# Base_Board_RevD.net
KiCad netlist of a schematic drawn in EAGLE
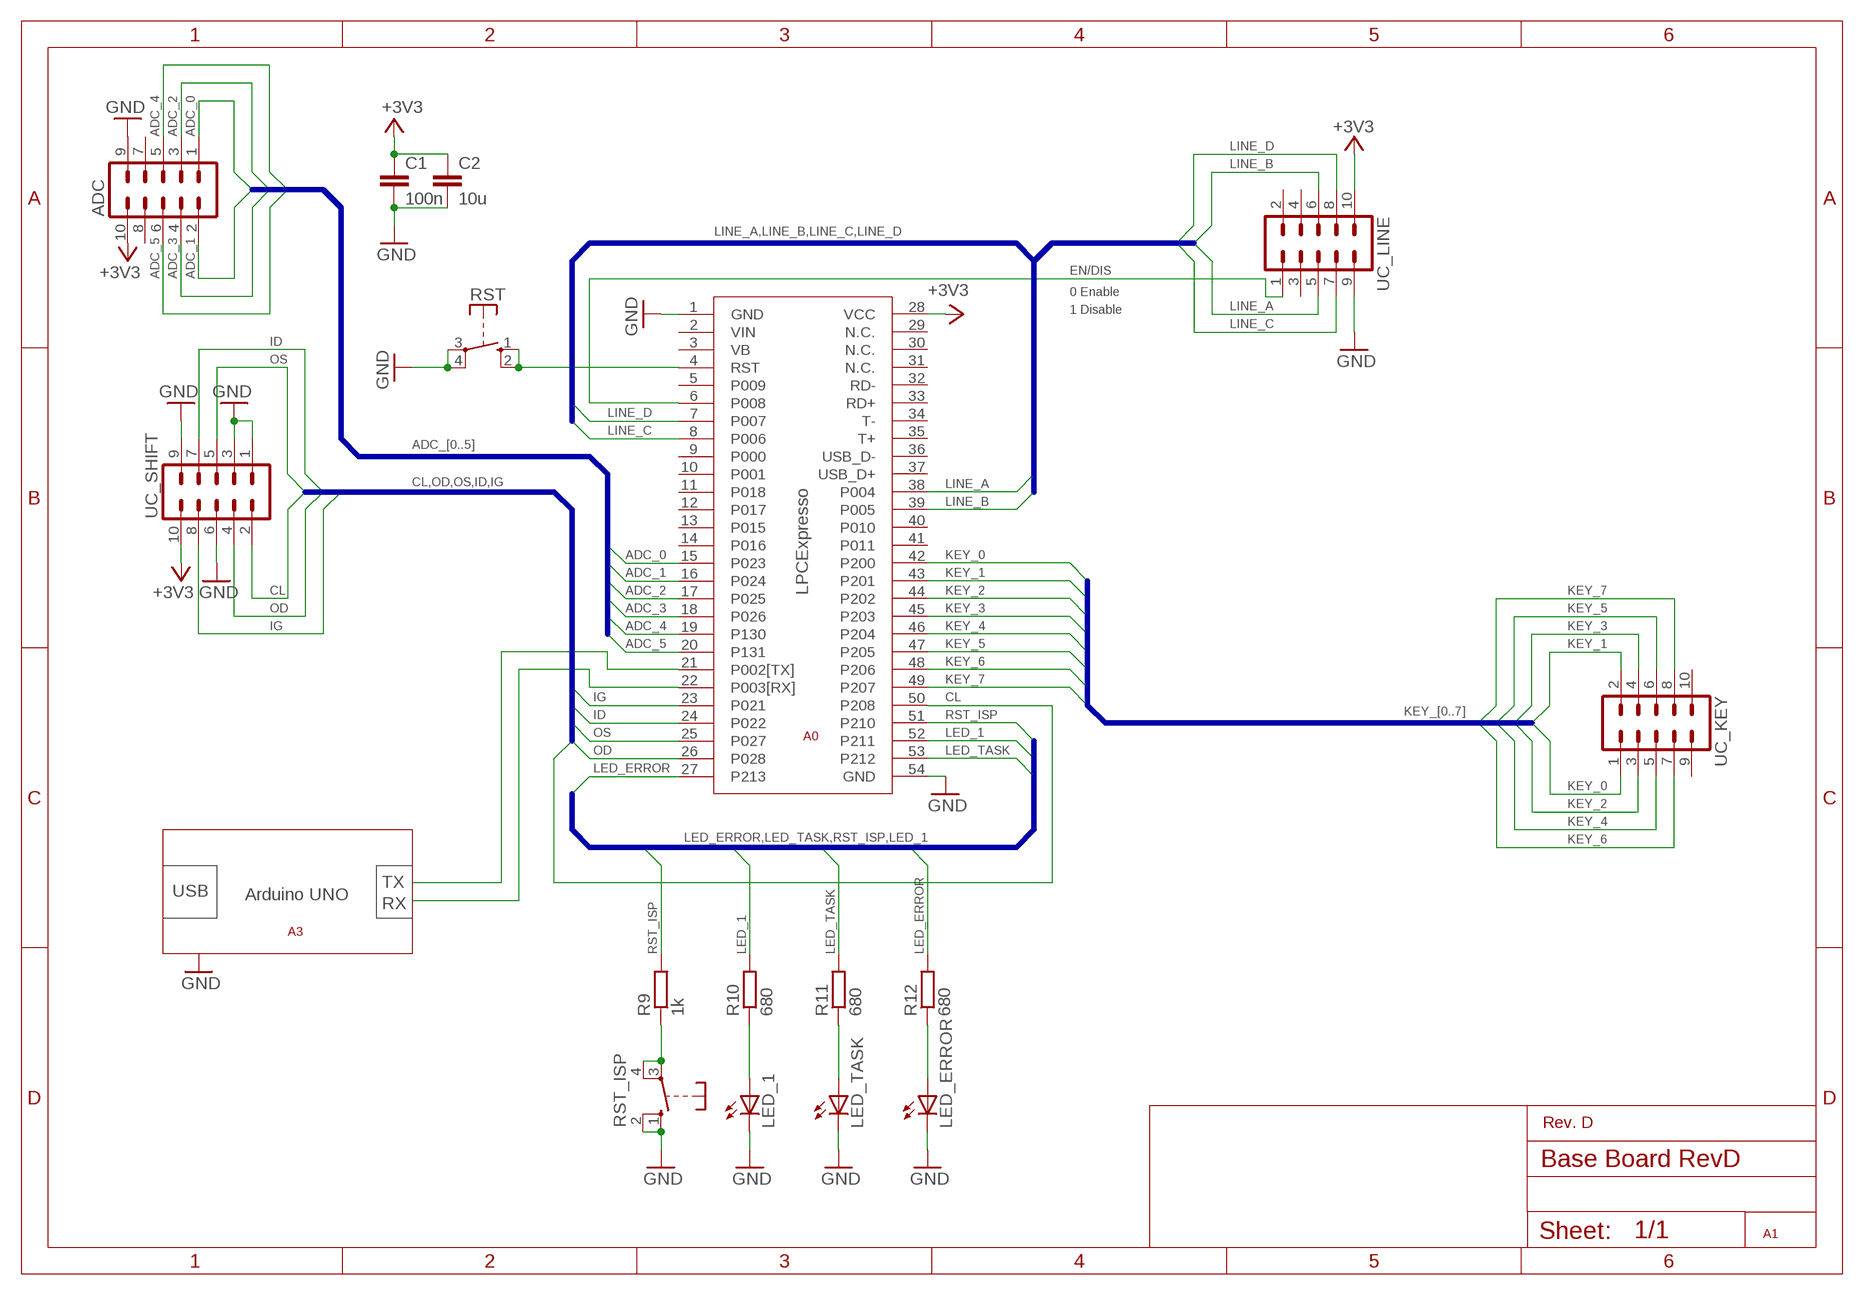
[diagram p0: schematic, sheet 1]

(export (version "E")
  (design (tool "Eeschema 10.0.6"))
  (components
    (comp (ref "ADC")
      (value "ML10")
      (footprint "eagle-import:ML10")
      (libsource (lib "eagle-import") (part "ML10"))
    )
    (comp (ref "C1")
      (value "100n")
      (footprint "eagle-import:C025-024X044")
      (libsource (lib "eagle-import") (part "C-EU025-024X044"))
    )
    (comp (ref "C2")
      (value "10u")
      (footprint "eagle-import:C025-024X044")
      (libsource (lib "eagle-import") (part "C-EU025-024X044"))
    )
    (comp (ref "LED_1")
      (value "LED5MM")
      (footprint "eagle-import:LED5MM")
      (libsource (lib "eagle-import") (part "LED5MM"))
    )
    (comp (ref "LED_ERROR")
      (value "LED5MM")
      (footprint "eagle-import:LED5MM")
      (libsource (lib "eagle-import") (part "LED5MM"))
    )
    (comp (ref "LED_TASK")
      (value "LED5MM")
      (footprint "eagle-import:LED5MM")
      (libsource (lib "eagle-import") (part "LED5MM"))
    )
    (comp (ref "R9")
      (value "1k")
      (footprint "eagle-import:0204_5")
      (libsource (lib "eagle-import") (part "R-EU_0204/5"))
    )
    (comp (ref "R10")
      (value "680")
      (footprint "eagle-import:0204_5")
      (libsource (lib "eagle-import") (part "R-EU_0204/5"))
    )
    (comp (ref "R11")
      (value "680")
      (footprint "eagle-import:0204_5")
      (libsource (lib "eagle-import") (part "R-EU_0204/5"))
    )
    (comp (ref "R12")
      (value "680")
      (footprint "eagle-import:0204_5")
      (libsource (lib "eagle-import") (part "R-EU_0204/5"))
    )
    (comp (ref "RST")
      (value "DT6")
      (footprint "eagle-import:DT6")
      (libsource (lib "eagle-import") (part "DT6"))
    )
    (comp (ref "RST_ISP")
      (value "DT6")
      (footprint "eagle-import:DT6")
      (libsource (lib "eagle-import") (part "DT6"))
    )
    (comp (ref "U$1")
      (value "LPCEXPRESSO")
      (footprint "eagle-import:LPCEXPRESSO")
      (libsource (lib "eagle-import") (part "LPCEXPRESSO"))
    )
    (comp (ref "UC_KEY")
      (value "ML10")
      (footprint "eagle-import:ML10")
      (libsource (lib "eagle-import") (part "ML10"))
    )
    (comp (ref "UC_LINE")
      (value "ML10")
      (footprint "eagle-import:ML10")
      (libsource (lib "eagle-import") (part "ML10"))
    )
    (comp (ref "UC_SHIFT")
      (value "ML10")
      (footprint "eagle-import:ML10")
      (libsource (lib "eagle-import") (part "ML10"))
    )
  )
  (nets
    (net (code "1") (name "+3V3") (class "Default")
      (node (ref "ADC") (pin "10") (pinfunction "10_10") (pintype "passive"))
      (node (ref "C1") (pin "1") (pinfunction "1_1") (pintype "passive"))
      (node (ref "C2") (pin "1") (pinfunction "1_1") (pintype "passive"))
      (node (ref "U$1") (pin "28") (pinfunction "VCC_28") (pintype "power_in"))
      (node (ref "UC_LINE") (pin "10") (pinfunction "10_10") (pintype "passive"))
      (node (ref "UC_SHIFT") (pin "10") (pinfunction "10_10") (pintype "passive"))
    )
    (net (code "2") (name "/ADC_0") (class "Default")
      (node (ref "ADC") (pin "1") (pinfunction "1_1") (pintype "passive"))
      (node (ref "U$1") (pin "15") (pinfunction "P023_15") (pintype "bidirectional"))
    )
    (net (code "3") (name "/ADC_1") (class "Default")
      (node (ref "ADC") (pin "2") (pinfunction "2_2") (pintype "passive"))
      (node (ref "U$1") (pin "16") (pinfunction "P024_16") (pintype "bidirectional"))
    )
    (net (code "4") (name "/ADC_2") (class "Default")
      (node (ref "ADC") (pin "3") (pinfunction "3_3") (pintype "passive"))
      (node (ref "U$1") (pin "17") (pinfunction "P025_17") (pintype "bidirectional"))
    )
    (net (code "5") (name "/ADC_3") (class "Default")
      (node (ref "ADC") (pin "4") (pinfunction "4_4") (pintype "passive"))
      (node (ref "U$1") (pin "18") (pinfunction "P026_18") (pintype "bidirectional"))
    )
    (net (code "6") (name "/ADC_4") (class "Default")
      (node (ref "ADC") (pin "5") (pinfunction "5_5") (pintype "passive"))
      (node (ref "U$1") (pin "19") (pinfunction "P130_19") (pintype "bidirectional"))
    )
    (net (code "7") (name "/ADC_5") (class "Default")
      (node (ref "ADC") (pin "6") (pinfunction "6_6") (pintype "passive"))
      (node (ref "U$1") (pin "20") (pinfunction "P131_20") (pintype "bidirectional"))
    )
    (net (code "9") (name "/CL") (class "Default")
      (node (ref "U$1") (pin "50") (pinfunction "P208_50") (pintype "bidirectional"))
      (node (ref "UC_SHIFT") (pin "2") (pinfunction "2_2") (pintype "passive"))
    )
    (net (code "10") (name "/EN{slash}DIS") (class "Default")
      (node (ref "U$1") (pin "6") (pinfunction "P008_6") (pintype "bidirectional"))
      (node (ref "UC_LINE") (pin "1") (pinfunction "1_1") (pintype "passive"))
    )
    (net (code "11") (name "/ID") (class "Default")
      (node (ref "U$1") (pin "24") (pinfunction "P022_24") (pintype "bidirectional"))
      (node (ref "UC_SHIFT") (pin "7") (pinfunction "7_7") (pintype "passive"))
    )
    (net (code "12") (name "/IG") (class "Default")
      (node (ref "U$1") (pin "23") (pinfunction "P021_23") (pintype "bidirectional"))
      (node (ref "UC_SHIFT") (pin "8") (pinfunction "8_8") (pintype "passive"))
    )
    (net (code "13") (name "/KEY_0") (class "Default")
      (node (ref "U$1") (pin "42") (pinfunction "P200_42") (pintype "bidirectional"))
      (node (ref "UC_KEY") (pin "1") (pinfunction "1_1") (pintype "passive"))
    )
    (net (code "14") (name "/KEY_1") (class "Default")
      (node (ref "U$1") (pin "43") (pinfunction "P201_43") (pintype "bidirectional"))
      (node (ref "UC_KEY") (pin "2") (pinfunction "2_2") (pintype "passive"))
    )
    (net (code "15") (name "/KEY_2") (class "Default")
      (node (ref "U$1") (pin "44") (pinfunction "P202_44") (pintype "bidirectional"))
      (node (ref "UC_KEY") (pin "3") (pinfunction "3_3") (pintype "passive"))
    )
    (net (code "16") (name "/KEY_3") (class "Default")
      (node (ref "U$1") (pin "45") (pinfunction "P203_45") (pintype "bidirectional"))
      (node (ref "UC_KEY") (pin "4") (pinfunction "4_4") (pintype "passive"))
    )
    (net (code "17") (name "/KEY_4") (class "Default")
      (node (ref "U$1") (pin "46") (pinfunction "P204_46") (pintype "bidirectional"))
      (node (ref "UC_KEY") (pin "5") (pinfunction "5_5") (pintype "passive"))
    )
    (net (code "18") (name "/KEY_5") (class "Default")
      (node (ref "U$1") (pin "47") (pinfunction "P205_47") (pintype "bidirectional"))
      (node (ref "UC_KEY") (pin "6") (pinfunction "6_6") (pintype "passive"))
    )
    (net (code "19") (name "/KEY_6") (class "Default")
      (node (ref "U$1") (pin "48") (pinfunction "P206_48") (pintype "bidirectional"))
      (node (ref "UC_KEY") (pin "7") (pinfunction "7_7") (pintype "passive"))
    )
    (net (code "20") (name "/KEY_7") (class "Default")
      (node (ref "U$1") (pin "49") (pinfunction "P207_49") (pintype "bidirectional"))
      (node (ref "UC_KEY") (pin "8") (pinfunction "8_8") (pintype "passive"))
    )
    (net (code "22") (name "/LED_1") (class "Default")
      (node (ref "R10") (pin "2") (pinfunction "2_2") (pintype "passive"))
      (node (ref "U$1") (pin "52") (pinfunction "P211_52") (pintype "bidirectional"))
    )
    (net (code "23") (name "/LED_ERROR") (class "Default")
      (node (ref "R12") (pin "2") (pinfunction "2_2") (pintype "passive"))
      (node (ref "U$1") (pin "27") (pinfunction "P213_27") (pintype "bidirectional"))
    )
    (net (code "24") (name "/LED_TASK") (class "Default")
      (node (ref "R11") (pin "2") (pinfunction "2_2") (pintype "passive"))
      (node (ref "U$1") (pin "53") (pinfunction "P212_53") (pintype "bidirectional"))
    )
    (net (code "25") (name "/LINE_A") (class "Default")
      (node (ref "U$1") (pin "38") (pinfunction "P004_38") (pintype "bidirectional"))
      (node (ref "UC_LINE") (pin "5") (pinfunction "5_5") (pintype "passive"))
    )
    (net (code "26") (name "/LINE_B") (class "Default")
      (node (ref "U$1") (pin "39") (pinfunction "P005_39") (pintype "bidirectional"))
      (node (ref "UC_LINE") (pin "6") (pinfunction "6_6") (pintype "passive"))
    )
    (net (code "27") (name "/LINE_C") (class "Default")
      (node (ref "U$1") (pin "8") (pinfunction "P006_8") (pintype "bidirectional"))
      (node (ref "UC_LINE") (pin "7") (pinfunction "7_7") (pintype "passive"))
    )
    (net (code "28") (name "/LINE_D") (class "Default")
      (node (ref "U$1") (pin "7") (pinfunction "P007_7") (pintype "bidirectional"))
      (node (ref "UC_LINE") (pin "8") (pinfunction "8_8") (pintype "passive"))
    )
    (net (code "29") (name "/OD") (class "Default")
      (node (ref "U$1") (pin "26") (pinfunction "P028_26") (pintype "bidirectional"))
      (node (ref "UC_SHIFT") (pin "4") (pinfunction "4_4") (pintype "passive"))
    )
    (net (code "30") (name "/OS") (class "Default")
      (node (ref "U$1") (pin "25") (pinfunction "P027_25") (pintype "bidirectional"))
      (node (ref "UC_SHIFT") (pin "5") (pinfunction "5_5") (pintype "passive"))
    )
    (net (code "31") (name "/RST_ISP") (class "Default")
      (node (ref "R9") (pin "2") (pinfunction "2_2") (pintype "passive"))
      (node (ref "U$1") (pin "51") (pinfunction "P210_51") (pintype "bidirectional"))
    )
    (net (code "32") (name "/VB") (class "Default")
      (node (ref "U$1") (pin "3") (pinfunction "VB_3") (pintype "power_in"))
    )
    (net (code "36") (name "GND") (class "Default")
      (node (ref "ADC") (pin "9") (pinfunction "9_9") (pintype "passive"))
      (node (ref "C1") (pin "2") (pinfunction "2_2") (pintype "passive"))
      (node (ref "C2") (pin "2") (pinfunction "2_2") (pintype "passive"))
      (node (ref "LED_1") (pin "K") (pinfunction "C_K") (pintype "passive"))
      (node (ref "LED_ERROR") (pin "K") (pinfunction "C_K") (pintype "passive"))
      (node (ref "LED_TASK") (pin "K") (pinfunction "C_K") (pintype "passive"))
      (node (ref "RST") (pin "3") (pinfunction "P_3") (pintype "passive"))
      (node (ref "RST") (pin "4") (pinfunction "P_4") (pintype "passive"))
      (node (ref "RST_ISP") (pin "1") (pinfunction "S_1") (pintype "passive"))
      (node (ref "RST_ISP") (pin "2") (pinfunction "S_2") (pintype "passive"))
      (node (ref "U$1") (pin "1") (pinfunction "GND_1") (pintype "power_in"))
      (node (ref "U$1") (pin "54") (pinfunction "GND_54") (pintype "power_in"))
      (node (ref "UC_LINE") (pin "9") (pinfunction "9_9") (pintype "passive"))
      (node (ref "UC_SHIFT") (pin "1") (pinfunction "1_1") (pintype "passive"))
      (node (ref "UC_SHIFT") (pin "3") (pinfunction "3_3") (pintype "passive"))
      (node (ref "UC_SHIFT") (pin "6") (pinfunction "6_6") (pintype "passive"))
      (node (ref "UC_SHIFT") (pin "9") (pinfunction "9_9") (pintype "passive"))
    )
    (net (code "37") (name "Net-(LED_1-PadA)") (class "Default")
      (node (ref "LED_1") (pin "A") (pinfunction "A_A") (pintype "passive"))
      (node (ref "R10") (pin "1") (pinfunction "1_1") (pintype "passive"))
    )
    (net (code "38") (name "Net-(LED_ERROR-PadA)") (class "Default")
      (node (ref "LED_ERROR") (pin "A") (pinfunction "A_A") (pintype "passive"))
      (node (ref "R12") (pin "1") (pinfunction "1_1") (pintype "passive"))
    )
    (net (code "39") (name "Net-(LED_TASK-PadA)") (class "Default")
      (node (ref "LED_TASK") (pin "A") (pinfunction "A_A") (pintype "passive"))
      (node (ref "R11") (pin "1") (pinfunction "1_1") (pintype "passive"))
    )
    (net (code "40") (name "Net-(R9-Pad1)") (class "Default")
      (node (ref "R9") (pin "1") (pinfunction "1_1") (pintype "passive"))
      (node (ref "RST_ISP") (pin "3") (pinfunction "P_3") (pintype "passive"))
      (node (ref "RST_ISP") (pin "4") (pinfunction "P_4") (pintype "passive"))
    )
    (net (code "41") (name "Net-(U$1-RST)") (class "Default")
      (node (ref "RST") (pin "1") (pinfunction "S_1") (pintype "passive"))
      (node (ref "RST") (pin "2") (pinfunction "S_2") (pintype "passive"))
      (node (ref "U$1") (pin "4") (pinfunction "RST_4") (pintype "bidirectional"))
    )
    (net (code "42") (name "unconnected-(ADC-Pad7)") (class "Default")
      (node (ref "ADC") (pin "7") (pinfunction "7_7") (pintype "passive"))
    )
    (net (code "43") (name "unconnected-(ADC-Pad8)") (class "Default")
      (node (ref "ADC") (pin "8") (pinfunction "8_8") (pintype "passive"))
    )
    (net (code "44") (name "unconnected-(U$1-N.C.-Pad29)") (class "Default")
      (node (ref "U$1") (pin "29") (pinfunction "N.C._29") (pintype "no_connect"))
    )
    (net (code "45") (name "unconnected-(U$1-N.C.-Pad30)") (class "Default")
      (node (ref "U$1") (pin "30") (pinfunction "N.C._30") (pintype "no_connect"))
    )
    (net (code "46") (name "unconnected-(U$1-N.C.-Pad31)") (class "Default")
      (node (ref "U$1") (pin "31") (pinfunction "N.C._31") (pintype "no_connect"))
    )
    (net (code "47") (name "unconnected-(U$1-P000-Pad9)") (class "Default")
      (node (ref "U$1") (pin "9") (pinfunction "P000_9") (pintype "bidirectional"))
    )
    (net (code "48") (name "unconnected-(U$1-P001-Pad10)") (class "Default")
      (node (ref "U$1") (pin "10") (pinfunction "P001_10") (pintype "bidirectional"))
    )
    (net (code "49") (name "unconnected-(U$1-P002[TX]-Pad21)") (class "Default")
      (node (ref "U$1") (pin "21") (pinfunction "P002[TX]_21") (pintype "bidirectional"))
    )
    (net (code "50") (name "unconnected-(U$1-P003[RX]-Pad22)") (class "Default")
      (node (ref "U$1") (pin "22") (pinfunction "P003[RX]_22") (pintype "bidirectional"))
    )
    (net (code "51") (name "unconnected-(U$1-P009-Pad5)") (class "Default")
      (node (ref "U$1") (pin "5") (pinfunction "P009_5") (pintype "bidirectional"))
    )
    (net (code "52") (name "unconnected-(U$1-P010-Pad40)") (class "Default")
      (node (ref "U$1") (pin "40") (pinfunction "P010_40") (pintype "bidirectional"))
    )
    (net (code "53") (name "unconnected-(U$1-P011-Pad41)") (class "Default")
      (node (ref "U$1") (pin "41") (pinfunction "P011_41") (pintype "bidirectional"))
    )
    (net (code "54") (name "unconnected-(U$1-P015-Pad13)") (class "Default")
      (node (ref "U$1") (pin "13") (pinfunction "P015_13") (pintype "bidirectional"))
    )
    (net (code "55") (name "unconnected-(U$1-P016-Pad14)") (class "Default")
      (node (ref "U$1") (pin "14") (pinfunction "P016_14") (pintype "bidirectional"))
    )
    (net (code "56") (name "unconnected-(U$1-P017-Pad12)") (class "Default")
      (node (ref "U$1") (pin "12") (pinfunction "P017_12") (pintype "bidirectional"))
    )
    (net (code "57") (name "unconnected-(U$1-P018-Pad11)") (class "Default")
      (node (ref "U$1") (pin "11") (pinfunction "P018_11") (pintype "bidirectional"))
    )
    (net (code "58") (name "unconnected-(U$1-RD+-Pad33)") (class "Default")
      (node (ref "U$1") (pin "33") (pinfunction "RD+_33") (pintype "bidirectional"))
    )
    (net (code "59") (name "unconnected-(U$1-RD--Pad32)") (class "Default")
      (node (ref "U$1") (pin "32") (pinfunction "RD-_32") (pintype "bidirectional"))
    )
    (net (code "60") (name "unconnected-(U$1-T+-Pad35)") (class "Default")
      (node (ref "U$1") (pin "35") (pinfunction "T+_35") (pintype "bidirectional"))
    )
    (net (code "61") (name "unconnected-(U$1-T--Pad34)") (class "Default")
      (node (ref "U$1") (pin "34") (pinfunction "T-_34") (pintype "bidirectional"))
    )
    (net (code "62") (name "unconnected-(U$1-USB_D+-Pad37)") (class "Default")
      (node (ref "U$1") (pin "37") (pinfunction "USB_D+_37") (pintype "bidirectional"))
    )
    (net (code "63") (name "unconnected-(U$1-USB_D--Pad36)") (class "Default")
      (node (ref "U$1") (pin "36") (pinfunction "USB_D-_36") (pintype "bidirectional"))
    )
    (net (code "64") (name "unconnected-(U$1-VIN-Pad2)") (class "Default")
      (node (ref "U$1") (pin "2") (pinfunction "VIN_2") (pintype "input"))
    )
    (net (code "65") (name "unconnected-(UC_KEY-Pad9)") (class "Default")
      (node (ref "UC_KEY") (pin "9") (pinfunction "9_9") (pintype "passive"))
    )
    (net (code "66") (name "unconnected-(UC_KEY-Pad10)") (class "Default")
      (node (ref "UC_KEY") (pin "10") (pinfunction "10_10") (pintype "passive"))
    )
    (net (code "67") (name "unconnected-(UC_LINE-Pad2)") (class "Default")
      (node (ref "UC_LINE") (pin "2") (pinfunction "2_2") (pintype "passive"))
    )
    (net (code "68") (name "unconnected-(UC_LINE-Pad3)") (class "Default")
      (node (ref "UC_LINE") (pin "3") (pinfunction "3_3") (pintype "passive"))
    )
    (net (code "69") (name "unconnected-(UC_LINE-Pad4)") (class "Default")
      (node (ref "UC_LINE") (pin "4") (pinfunction "4_4") (pintype "passive"))
    )
  )
)
